# hundredsteppers.net
KiCad netlist of a schematic drawn in EAGLE
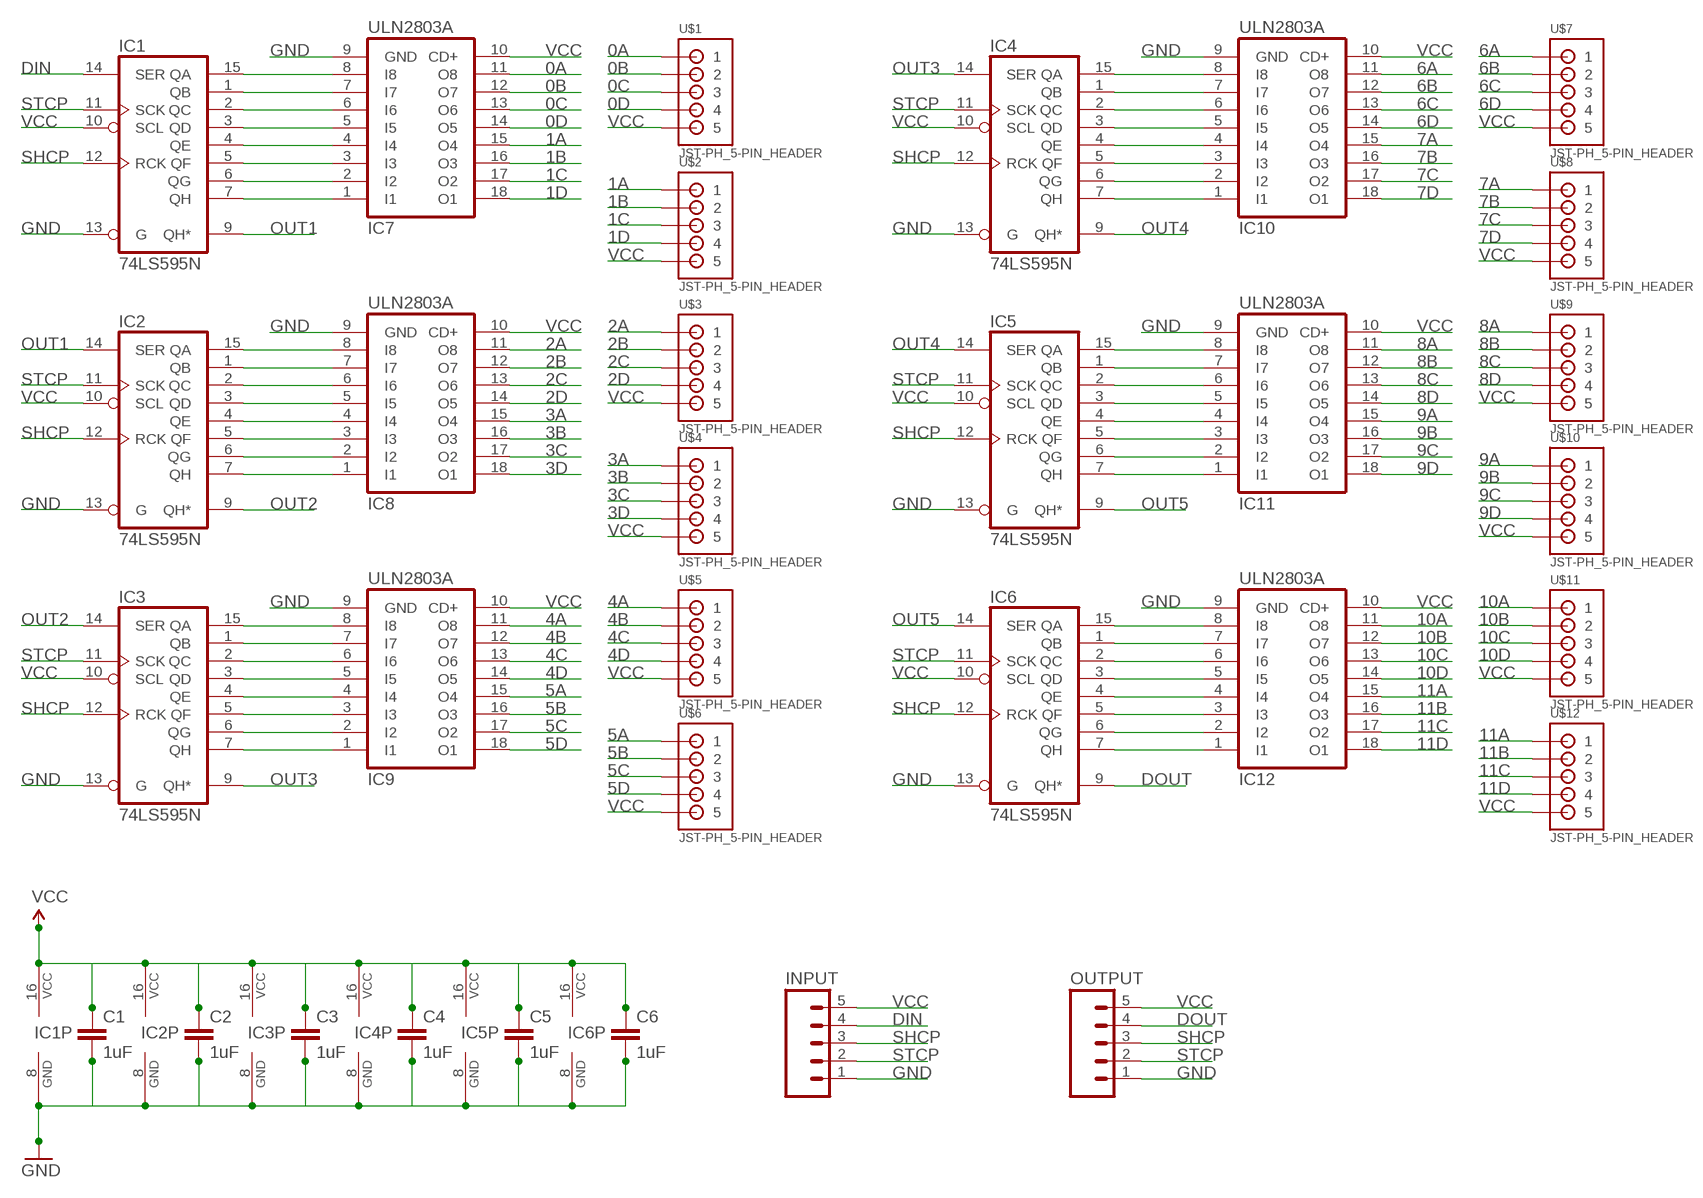
[diagram p0: schematic, sheet 1]

(export (version "E")
  (design (tool "Eeschema 10.0.6"))
  (components
    (comp (ref "C1")
      (value "1uF")
      (footprint "eagle-import:0805")
      (libsource (lib "eagle-import") (part "1UF-25V-10%(0805)"))
    )
    (comp (ref "C2")
      (value "1uF")
      (footprint "eagle-import:0805")
      (libsource (lib "eagle-import") (part "1UF-25V-10%(0805)"))
    )
    (comp (ref "C3")
      (value "1uF")
      (footprint "eagle-import:0805")
      (libsource (lib "eagle-import") (part "1UF-25V-10%(0805)"))
    )
    (comp (ref "C4")
      (value "1uF")
      (footprint "eagle-import:0805")
      (libsource (lib "eagle-import") (part "1UF-25V-10%(0805)"))
    )
    (comp (ref "C5")
      (value "1uF")
      (footprint "eagle-import:0805")
      (libsource (lib "eagle-import") (part "1UF-25V-10%(0805)"))
    )
    (comp (ref "C6")
      (value "1uF")
      (footprint "eagle-import:0805")
      (libsource (lib "eagle-import") (part "1UF-25V-10%(0805)"))
    )
    (comp (ref "IC1")
      (value "74LS595N")
      (footprint "eagle-import:DIL16")
      (libsource (lib "eagle-import") (part "74595NLS"))
    )
    (comp (ref "IC2")
      (value "74LS595N")
      (footprint "eagle-import:DIL16")
      (libsource (lib "eagle-import") (part "74595NLS"))
    )
    (comp (ref "IC3")
      (value "74LS595N")
      (footprint "eagle-import:DIL16")
      (libsource (lib "eagle-import") (part "74595NLS"))
    )
    (comp (ref "IC4")
      (value "74LS595N")
      (footprint "eagle-import:DIL16")
      (libsource (lib "eagle-import") (part "74595NLS"))
    )
    (comp (ref "IC5")
      (value "74LS595N")
      (footprint "eagle-import:DIL16")
      (libsource (lib "eagle-import") (part "74595NLS"))
    )
    (comp (ref "IC6")
      (value "74LS595N")
      (footprint "eagle-import:DIL16")
      (libsource (lib "eagle-import") (part "74595NLS"))
    )
    (comp (ref "IC7")
      (value "ULN2803A")
      (footprint "eagle-import:DIL18")
      (libsource (lib "eagle-import") (part "ULN2803A"))
    )
    (comp (ref "IC8")
      (value "ULN2803A")
      (footprint "eagle-import:DIL18")
      (libsource (lib "eagle-import") (part "ULN2803A"))
    )
    (comp (ref "IC9")
      (value "ULN2803A")
      (footprint "eagle-import:DIL18")
      (libsource (lib "eagle-import") (part "ULN2803A"))
    )
    (comp (ref "IC10")
      (value "ULN2803A")
      (footprint "eagle-import:DIL18")
      (libsource (lib "eagle-import") (part "ULN2803A"))
    )
    (comp (ref "IC11")
      (value "ULN2803A")
      (footprint "eagle-import:DIL18")
      (libsource (lib "eagle-import") (part "ULN2803A"))
    )
    (comp (ref "IC12")
      (value "ULN2803A")
      (footprint "eagle-import:DIL18")
      (libsource (lib "eagle-import") (part "ULN2803A"))
    )
    (comp (ref "INPUT")
      (value "M05PTH")
      (footprint "eagle-import:1X05")
      (libsource (lib "eagle-import") (part "M05PTH"))
    )
    (comp (ref "OUTPUT")
      (value "M05PTH")
      (footprint "eagle-import:1X05")
      (libsource (lib "eagle-import") (part "M05PTH"))
    )
    (comp (ref "U$1")
      (value "JST-PH_5-PIN_HEADER")
      (footprint "eagle-import:JST_B5B-PH_HEADER")
      (libsource (lib "eagle-import") (part "JST-PH_5-PIN_HEADER"))
    )
    (comp (ref "U$2")
      (value "JST-PH_5-PIN_HEADER")
      (footprint "eagle-import:JST_B5B-PH_HEADER")
      (libsource (lib "eagle-import") (part "JST-PH_5-PIN_HEADER"))
    )
    (comp (ref "U$3")
      (value "JST-PH_5-PIN_HEADER")
      (footprint "eagle-import:JST_B5B-PH_HEADER")
      (libsource (lib "eagle-import") (part "JST-PH_5-PIN_HEADER"))
    )
    (comp (ref "U$4")
      (value "JST-PH_5-PIN_HEADER")
      (footprint "eagle-import:JST_B5B-PH_HEADER")
      (libsource (lib "eagle-import") (part "JST-PH_5-PIN_HEADER"))
    )
    (comp (ref "U$5")
      (value "JST-PH_5-PIN_HEADER")
      (footprint "eagle-import:JST_B5B-PH_HEADER")
      (libsource (lib "eagle-import") (part "JST-PH_5-PIN_HEADER"))
    )
    (comp (ref "U$6")
      (value "JST-PH_5-PIN_HEADER")
      (footprint "eagle-import:JST_B5B-PH_HEADER")
      (libsource (lib "eagle-import") (part "JST-PH_5-PIN_HEADER"))
    )
    (comp (ref "U$7")
      (value "JST-PH_5-PIN_HEADER")
      (footprint "eagle-import:JST_B5B-PH_HEADER")
      (libsource (lib "eagle-import") (part "JST-PH_5-PIN_HEADER"))
    )
    (comp (ref "U$8")
      (value "JST-PH_5-PIN_HEADER")
      (footprint "eagle-import:JST_B5B-PH_HEADER")
      (libsource (lib "eagle-import") (part "JST-PH_5-PIN_HEADER"))
    )
    (comp (ref "U$9")
      (value "JST-PH_5-PIN_HEADER")
      (footprint "eagle-import:JST_B5B-PH_HEADER")
      (libsource (lib "eagle-import") (part "JST-PH_5-PIN_HEADER"))
    )
    (comp (ref "U$10")
      (value "JST-PH_5-PIN_HEADER")
      (footprint "eagle-import:JST_B5B-PH_HEADER")
      (libsource (lib "eagle-import") (part "JST-PH_5-PIN_HEADER"))
    )
    (comp (ref "U$11")
      (value "JST-PH_5-PIN_HEADER")
      (footprint "eagle-import:JST_B5B-PH_HEADER")
      (libsource (lib "eagle-import") (part "JST-PH_5-PIN_HEADER"))
    )
    (comp (ref "U$12")
      (value "JST-PH_5-PIN_HEADER")
      (footprint "eagle-import:JST_B5B-PH_HEADER")
      (libsource (lib "eagle-import") (part "JST-PH_5-PIN_HEADER"))
    )
  )
  (nets
    (net (code "1") (name "/0A") (class "Default")
      (node (ref "IC7") (pin "11") (pinfunction "O8_11") (pintype "open_collector"))
      (node (ref "U$1") (pin "P1") (pinfunction "1_P1") (pintype "bidirectional"))
    )
    (net (code "2") (name "/0B") (class "Default")
      (node (ref "IC7") (pin "12") (pinfunction "O7_12") (pintype "open_collector"))
      (node (ref "U$1") (pin "P2") (pinfunction "2_P2") (pintype "bidirectional"))
    )
    (net (code "3") (name "/0C") (class "Default")
      (node (ref "IC7") (pin "13") (pinfunction "O6_13") (pintype "open_collector"))
      (node (ref "U$1") (pin "P3") (pinfunction "3_P3") (pintype "bidirectional"))
    )
    (net (code "4") (name "/0D") (class "Default")
      (node (ref "IC7") (pin "14") (pinfunction "O5_14") (pintype "open_collector"))
      (node (ref "U$1") (pin "P4") (pinfunction "4_P4") (pintype "bidirectional"))
    )
    (net (code "5") (name "/1A") (class "Default")
      (node (ref "IC7") (pin "15") (pinfunction "O4_15") (pintype "open_collector"))
      (node (ref "U$2") (pin "P1") (pinfunction "1_P1") (pintype "bidirectional"))
    )
    (net (code "6") (name "/1B") (class "Default")
      (node (ref "IC7") (pin "16") (pinfunction "O3_16") (pintype "open_collector"))
      (node (ref "U$2") (pin "P2") (pinfunction "2_P2") (pintype "bidirectional"))
    )
    (net (code "7") (name "/1C") (class "Default")
      (node (ref "IC7") (pin "17") (pinfunction "O2_17") (pintype "open_collector"))
      (node (ref "U$2") (pin "P3") (pinfunction "3_P3") (pintype "bidirectional"))
    )
    (net (code "8") (name "/1D") (class "Default")
      (node (ref "IC7") (pin "18") (pinfunction "O1_18") (pintype "open_collector"))
      (node (ref "U$2") (pin "P4") (pinfunction "4_P4") (pintype "bidirectional"))
    )
    (net (code "9") (name "/2A") (class "Default")
      (node (ref "IC8") (pin "11") (pinfunction "O8_11") (pintype "open_collector"))
      (node (ref "U$3") (pin "P1") (pinfunction "1_P1") (pintype "bidirectional"))
    )
    (net (code "10") (name "/2B") (class "Default")
      (node (ref "IC8") (pin "12") (pinfunction "O7_12") (pintype "open_collector"))
      (node (ref "U$3") (pin "P2") (pinfunction "2_P2") (pintype "bidirectional"))
    )
    (net (code "11") (name "/2C") (class "Default")
      (node (ref "IC8") (pin "13") (pinfunction "O6_13") (pintype "open_collector"))
      (node (ref "U$3") (pin "P3") (pinfunction "3_P3") (pintype "bidirectional"))
    )
    (net (code "12") (name "/2D") (class "Default")
      (node (ref "IC8") (pin "14") (pinfunction "O5_14") (pintype "open_collector"))
      (node (ref "U$3") (pin "P4") (pinfunction "4_P4") (pintype "bidirectional"))
    )
    (net (code "13") (name "/3A") (class "Default")
      (node (ref "IC8") (pin "15") (pinfunction "O4_15") (pintype "open_collector"))
      (node (ref "U$4") (pin "P1") (pinfunction "1_P1") (pintype "bidirectional"))
    )
    (net (code "14") (name "/3B") (class "Default")
      (node (ref "IC8") (pin "16") (pinfunction "O3_16") (pintype "open_collector"))
      (node (ref "U$4") (pin "P2") (pinfunction "2_P2") (pintype "bidirectional"))
    )
    (net (code "15") (name "/3C") (class "Default")
      (node (ref "IC8") (pin "17") (pinfunction "O2_17") (pintype "open_collector"))
      (node (ref "U$4") (pin "P3") (pinfunction "3_P3") (pintype "bidirectional"))
    )
    (net (code "16") (name "/3D") (class "Default")
      (node (ref "IC8") (pin "18") (pinfunction "O1_18") (pintype "open_collector"))
      (node (ref "U$4") (pin "P4") (pinfunction "4_P4") (pintype "bidirectional"))
    )
    (net (code "17") (name "/4A") (class "Default")
      (node (ref "IC9") (pin "11") (pinfunction "O8_11") (pintype "open_collector"))
      (node (ref "U$5") (pin "P1") (pinfunction "1_P1") (pintype "bidirectional"))
    )
    (net (code "18") (name "/4B") (class "Default")
      (node (ref "IC9") (pin "12") (pinfunction "O7_12") (pintype "open_collector"))
      (node (ref "U$5") (pin "P2") (pinfunction "2_P2") (pintype "bidirectional"))
    )
    (net (code "19") (name "/4C") (class "Default")
      (node (ref "IC9") (pin "13") (pinfunction "O6_13") (pintype "open_collector"))
      (node (ref "U$5") (pin "P3") (pinfunction "3_P3") (pintype "bidirectional"))
    )
    (net (code "20") (name "/4D") (class "Default")
      (node (ref "IC9") (pin "14") (pinfunction "O5_14") (pintype "open_collector"))
      (node (ref "U$5") (pin "P4") (pinfunction "4_P4") (pintype "bidirectional"))
    )
    (net (code "21") (name "/5A") (class "Default")
      (node (ref "IC9") (pin "15") (pinfunction "O4_15") (pintype "open_collector"))
      (node (ref "U$6") (pin "P1") (pinfunction "1_P1") (pintype "bidirectional"))
    )
    (net (code "22") (name "/5B") (class "Default")
      (node (ref "IC9") (pin "16") (pinfunction "O3_16") (pintype "open_collector"))
      (node (ref "U$6") (pin "P2") (pinfunction "2_P2") (pintype "bidirectional"))
    )
    (net (code "23") (name "/5C") (class "Default")
      (node (ref "IC9") (pin "17") (pinfunction "O2_17") (pintype "open_collector"))
      (node (ref "U$6") (pin "P3") (pinfunction "3_P3") (pintype "bidirectional"))
    )
    (net (code "24") (name "/5D") (class "Default")
      (node (ref "IC9") (pin "18") (pinfunction "O1_18") (pintype "open_collector"))
      (node (ref "U$6") (pin "P4") (pinfunction "4_P4") (pintype "bidirectional"))
    )
    (net (code "25") (name "/6A") (class "Default")
      (node (ref "IC10") (pin "11") (pinfunction "O8_11") (pintype "open_collector"))
      (node (ref "U$7") (pin "P1") (pinfunction "1_P1") (pintype "bidirectional"))
    )
    (net (code "26") (name "/6B") (class "Default")
      (node (ref "IC10") (pin "12") (pinfunction "O7_12") (pintype "open_collector"))
      (node (ref "U$7") (pin "P2") (pinfunction "2_P2") (pintype "bidirectional"))
    )
    (net (code "27") (name "/6C") (class "Default")
      (node (ref "IC10") (pin "13") (pinfunction "O6_13") (pintype "open_collector"))
      (node (ref "U$7") (pin "P3") (pinfunction "3_P3") (pintype "bidirectional"))
    )
    (net (code "28") (name "/6D") (class "Default")
      (node (ref "IC10") (pin "14") (pinfunction "O5_14") (pintype "open_collector"))
      (node (ref "U$7") (pin "P4") (pinfunction "4_P4") (pintype "bidirectional"))
    )
    (net (code "29") (name "/7A") (class "Default")
      (node (ref "IC10") (pin "15") (pinfunction "O4_15") (pintype "open_collector"))
      (node (ref "U$8") (pin "P1") (pinfunction "1_P1") (pintype "bidirectional"))
    )
    (net (code "30") (name "/7B") (class "Default")
      (node (ref "IC10") (pin "16") (pinfunction "O3_16") (pintype "open_collector"))
      (node (ref "U$8") (pin "P2") (pinfunction "2_P2") (pintype "bidirectional"))
    )
    (net (code "31") (name "/7C") (class "Default")
      (node (ref "IC10") (pin "17") (pinfunction "O2_17") (pintype "open_collector"))
      (node (ref "U$8") (pin "P3") (pinfunction "3_P3") (pintype "bidirectional"))
    )
    (net (code "32") (name "/7D") (class "Default")
      (node (ref "IC10") (pin "18") (pinfunction "O1_18") (pintype "open_collector"))
      (node (ref "U$8") (pin "P4") (pinfunction "4_P4") (pintype "bidirectional"))
    )
    (net (code "33") (name "/8A") (class "Default")
      (node (ref "IC11") (pin "11") (pinfunction "O8_11") (pintype "open_collector"))
      (node (ref "U$9") (pin "P1") (pinfunction "1_P1") (pintype "bidirectional"))
    )
    (net (code "34") (name "/8B") (class "Default")
      (node (ref "IC11") (pin "12") (pinfunction "O7_12") (pintype "open_collector"))
      (node (ref "U$9") (pin "P2") (pinfunction "2_P2") (pintype "bidirectional"))
    )
    (net (code "35") (name "/8C") (class "Default")
      (node (ref "IC11") (pin "13") (pinfunction "O6_13") (pintype "open_collector"))
      (node (ref "U$9") (pin "P3") (pinfunction "3_P3") (pintype "bidirectional"))
    )
    (net (code "36") (name "/8D") (class "Default")
      (node (ref "IC11") (pin "14") (pinfunction "O5_14") (pintype "open_collector"))
      (node (ref "U$9") (pin "P4") (pinfunction "4_P4") (pintype "bidirectional"))
    )
    (net (code "37") (name "/9A") (class "Default")
      (node (ref "IC11") (pin "15") (pinfunction "O4_15") (pintype "open_collector"))
      (node (ref "U$10") (pin "P1") (pinfunction "1_P1") (pintype "bidirectional"))
    )
    (net (code "38") (name "/9B") (class "Default")
      (node (ref "IC11") (pin "16") (pinfunction "O3_16") (pintype "open_collector"))
      (node (ref "U$10") (pin "P2") (pinfunction "2_P2") (pintype "bidirectional"))
    )
    (net (code "39") (name "/9C") (class "Default")
      (node (ref "IC11") (pin "17") (pinfunction "O2_17") (pintype "open_collector"))
      (node (ref "U$10") (pin "P3") (pinfunction "3_P3") (pintype "bidirectional"))
    )
    (net (code "40") (name "/9D") (class "Default")
      (node (ref "IC11") (pin "18") (pinfunction "O1_18") (pintype "open_collector"))
      (node (ref "U$10") (pin "P4") (pinfunction "4_P4") (pintype "bidirectional"))
    )
    (net (code "41") (name "/10A") (class "Default")
      (node (ref "IC12") (pin "11") (pinfunction "O8_11") (pintype "open_collector"))
      (node (ref "U$11") (pin "P1") (pinfunction "1_P1") (pintype "bidirectional"))
    )
    (net (code "42") (name "/10B") (class "Default")
      (node (ref "IC12") (pin "12") (pinfunction "O7_12") (pintype "open_collector"))
      (node (ref "U$11") (pin "P2") (pinfunction "2_P2") (pintype "bidirectional"))
    )
    (net (code "43") (name "/10C") (class "Default")
      (node (ref "IC12") (pin "13") (pinfunction "O6_13") (pintype "open_collector"))
      (node (ref "U$11") (pin "P3") (pinfunction "3_P3") (pintype "bidirectional"))
    )
    (net (code "44") (name "/10D") (class "Default")
      (node (ref "IC12") (pin "14") (pinfunction "O5_14") (pintype "open_collector"))
      (node (ref "U$11") (pin "P4") (pinfunction "4_P4") (pintype "bidirectional"))
    )
    (net (code "45") (name "/11A") (class "Default")
      (node (ref "IC12") (pin "15") (pinfunction "O4_15") (pintype "open_collector"))
      (node (ref "U$12") (pin "P1") (pinfunction "1_P1") (pintype "bidirectional"))
    )
    (net (code "46") (name "/11B") (class "Default")
      (node (ref "IC12") (pin "16") (pinfunction "O3_16") (pintype "open_collector"))
      (node (ref "U$12") (pin "P2") (pinfunction "2_P2") (pintype "bidirectional"))
    )
    (net (code "47") (name "/11C") (class "Default")
      (node (ref "IC12") (pin "17") (pinfunction "O2_17") (pintype "open_collector"))
      (node (ref "U$12") (pin "P3") (pinfunction "3_P3") (pintype "bidirectional"))
    )
    (net (code "48") (name "/11D") (class "Default")
      (node (ref "IC12") (pin "18") (pinfunction "O1_18") (pintype "open_collector"))
      (node (ref "U$12") (pin "P4") (pinfunction "4_P4") (pintype "bidirectional"))
    )
    (net (code "49") (name "/DIN") (class "Default")
      (node (ref "IC1") (pin "14") (pinfunction "SER_14") (pintype "input"))
      (node (ref "INPUT") (pin "4") (pinfunction "4_4") (pintype "passive"))
    )
    (net (code "50") (name "/DOUT") (class "Default")
      (node (ref "IC6") (pin "9") (pinfunction "QH*_9") (pintype "tri_state"))
      (node (ref "OUTPUT") (pin "4") (pinfunction "4_4") (pintype "passive"))
    )
    (net (code "51") (name "/OUT1") (class "Default")
      (node (ref "IC1") (pin "9") (pinfunction "QH*_9") (pintype "tri_state"))
      (node (ref "IC2") (pin "14") (pinfunction "SER_14") (pintype "input"))
    )
    (net (code "52") (name "/OUT2") (class "Default")
      (node (ref "IC2") (pin "9") (pinfunction "QH*_9") (pintype "tri_state"))
      (node (ref "IC3") (pin "14") (pinfunction "SER_14") (pintype "input"))
    )
    (net (code "53") (name "/OUT3") (class "Default")
      (node (ref "IC3") (pin "9") (pinfunction "QH*_9") (pintype "tri_state"))
      (node (ref "IC4") (pin "14") (pinfunction "SER_14") (pintype "input"))
    )
    (net (code "54") (name "/OUT4") (class "Default")
      (node (ref "IC4") (pin "9") (pinfunction "QH*_9") (pintype "tri_state"))
      (node (ref "IC5") (pin "14") (pinfunction "SER_14") (pintype "input"))
    )
    (net (code "55") (name "/OUT5") (class "Default")
      (node (ref "IC5") (pin "9") (pinfunction "QH*_9") (pintype "tri_state"))
      (node (ref "IC6") (pin "14") (pinfunction "SER_14") (pintype "input"))
    )
    (net (code "56") (name "/SHCP") (class "Default")
      (node (ref "IC1") (pin "12") (pinfunction "RCK_12") (pintype "input"))
      (node (ref "IC2") (pin "12") (pinfunction "RCK_12") (pintype "input"))
      (node (ref "IC3") (pin "12") (pinfunction "RCK_12") (pintype "input"))
      (node (ref "IC4") (pin "12") (pinfunction "RCK_12") (pintype "input"))
      (node (ref "IC5") (pin "12") (pinfunction "RCK_12") (pintype "input"))
      (node (ref "IC6") (pin "12") (pinfunction "RCK_12") (pintype "input"))
      (node (ref "INPUT") (pin "3") (pinfunction "3_3") (pintype "passive"))
      (node (ref "OUTPUT") (pin "3") (pinfunction "3_3") (pintype "passive"))
    )
    (net (code "57") (name "/STCP") (class "Default")
      (node (ref "IC1") (pin "11") (pinfunction "SCK_11") (pintype "input"))
      (node (ref "IC2") (pin "11") (pinfunction "SCK_11") (pintype "input"))
      (node (ref "IC3") (pin "11") (pinfunction "SCK_11") (pintype "input"))
      (node (ref "IC4") (pin "11") (pinfunction "SCK_11") (pintype "input"))
      (node (ref "IC5") (pin "11") (pinfunction "SCK_11") (pintype "input"))
      (node (ref "IC6") (pin "11") (pinfunction "SCK_11") (pintype "input"))
      (node (ref "INPUT") (pin "2") (pinfunction "2_2") (pintype "passive"))
      (node (ref "OUTPUT") (pin "2") (pinfunction "2_2") (pintype "passive"))
    )
    (net (code "58") (name "GND") (class "Default")
      (node (ref "C1") (pin "2") (pinfunction "2_2") (pintype "passive"))
      (node (ref "C2") (pin "2") (pinfunction "2_2") (pintype "passive"))
      (node (ref "C3") (pin "2") (pinfunction "2_2") (pintype "passive"))
      (node (ref "C4") (pin "2") (pinfunction "2_2") (pintype "passive"))
      (node (ref "C5") (pin "2") (pinfunction "2_2") (pintype "passive"))
      (node (ref "C6") (pin "2") (pinfunction "2_2") (pintype "passive"))
      (node (ref "IC1") (pin "13") (pinfunction "G_13") (pintype "input"))
      (node (ref "IC1") (pin "8") (pinfunction "GND_8") (pintype "power_in"))
      (node (ref "IC10") (pin "9") (pinfunction "GND_9") (pintype "power_in"))
      (node (ref "IC11") (pin "9") (pinfunction "GND_9") (pintype "power_in"))
      (node (ref "IC12") (pin "9") (pinfunction "GND_9") (pintype "power_in"))
      (node (ref "IC2") (pin "13") (pinfunction "G_13") (pintype "input"))
      (node (ref "IC2") (pin "8") (pinfunction "GND_8") (pintype "power_in"))
      (node (ref "IC3") (pin "13") (pinfunction "G_13") (pintype "input"))
      (node (ref "IC3") (pin "8") (pinfunction "GND_8") (pintype "power_in"))
      (node (ref "IC4") (pin "13") (pinfunction "G_13") (pintype "input"))
      (node (ref "IC4") (pin "8") (pinfunction "GND_8") (pintype "power_in"))
      (node (ref "IC5") (pin "13") (pinfunction "G_13") (pintype "input"))
      (node (ref "IC5") (pin "8") (pinfunction "GND_8") (pintype "power_in"))
      (node (ref "IC6") (pin "13") (pinfunction "G_13") (pintype "input"))
      (node (ref "IC6") (pin "8") (pinfunction "GND_8") (pintype "power_in"))
      (node (ref "IC7") (pin "9") (pinfunction "GND_9") (pintype "power_in"))
      (node (ref "IC8") (pin "9") (pinfunction "GND_9") (pintype "power_in"))
      (node (ref "IC9") (pin "9") (pinfunction "GND_9") (pintype "power_in"))
      (node (ref "INPUT") (pin "1") (pinfunction "1_1") (pintype "passive"))
      (node (ref "OUTPUT") (pin "1") (pinfunction "1_1") (pintype "passive"))
    )
    (net (code "59") (name "Net-(IC1A-QA)") (class "Default")
      (node (ref "IC1") (pin "15") (pinfunction "QA_15") (pintype "tri_state"))
      (node (ref "IC7") (pin "8") (pinfunction "I8_8") (pintype "input"))
    )
    (net (code "60") (name "Net-(IC1A-QB)") (class "Default")
      (node (ref "IC1") (pin "1") (pinfunction "QB_1") (pintype "tri_state"))
      (node (ref "IC7") (pin "7") (pinfunction "I7_7") (pintype "input"))
    )
    (net (code "61") (name "Net-(IC1A-QC)") (class "Default")
      (node (ref "IC1") (pin "2") (pinfunction "QC_2") (pintype "tri_state"))
      (node (ref "IC7") (pin "6") (pinfunction "I6_6") (pintype "input"))
    )
    (net (code "62") (name "Net-(IC1A-QD)") (class "Default")
      (node (ref "IC1") (pin "3") (pinfunction "QD_3") (pintype "tri_state"))
      (node (ref "IC7") (pin "5") (pinfunction "I5_5") (pintype "input"))
    )
    (net (code "63") (name "Net-(IC1A-QE)") (class "Default")
      (node (ref "IC1") (pin "4") (pinfunction "QE_4") (pintype "tri_state"))
      (node (ref "IC7") (pin "4") (pinfunction "I4_4") (pintype "input"))
    )
    (net (code "64") (name "Net-(IC1A-QF)") (class "Default")
      (node (ref "IC1") (pin "5") (pinfunction "QF_5") (pintype "tri_state"))
      (node (ref "IC7") (pin "3") (pinfunction "I3_3") (pintype "input"))
    )
    (net (code "65") (name "Net-(IC1A-QG)") (class "Default")
      (node (ref "IC1") (pin "6") (pinfunction "QG_6") (pintype "tri_state"))
      (node (ref "IC7") (pin "2") (pinfunction "I2_2") (pintype "input"))
    )
    (net (code "66") (name "Net-(IC1A-QH)") (class "Default")
      (node (ref "IC1") (pin "7") (pinfunction "QH_7") (pintype "tri_state"))
      (node (ref "IC7") (pin "1") (pinfunction "I1_1") (pintype "input"))
    )
    (net (code "67") (name "Net-(IC2A-QA)") (class "Default")
      (node (ref "IC2") (pin "15") (pinfunction "QA_15") (pintype "tri_state"))
      (node (ref "IC8") (pin "8") (pinfunction "I8_8") (pintype "input"))
    )
    (net (code "68") (name "Net-(IC2A-QB)") (class "Default")
      (node (ref "IC2") (pin "1") (pinfunction "QB_1") (pintype "tri_state"))
      (node (ref "IC8") (pin "7") (pinfunction "I7_7") (pintype "input"))
    )
    (net (code "69") (name "Net-(IC2A-QC)") (class "Default")
      (node (ref "IC2") (pin "2") (pinfunction "QC_2") (pintype "tri_state"))
      (node (ref "IC8") (pin "6") (pinfunction "I6_6") (pintype "input"))
    )
    (net (code "70") (name "Net-(IC2A-QD)") (class "Default")
      (node (ref "IC2") (pin "3") (pinfunction "QD_3") (pintype "tri_state"))
      (node (ref "IC8") (pin "5") (pinfunction "I5_5") (pintype "input"))
    )
    (net (code "71") (name "Net-(IC2A-QE)") (class "Default")
      (node (ref "IC2") (pin "4") (pinfunction "QE_4") (pintype "tri_state"))
      (node (ref "IC8") (pin "4") (pinfunction "I4_4") (pintype "input"))
    )
    (net (code "72") (name "Net-(IC2A-QF)") (class "Default")
      (node (ref "IC2") (pin "5") (pinfunction "QF_5") (pintype "tri_state"))
      (node (ref "IC8") (pin "3") (pinfunction "I3_3") (pintype "input"))
    )
    (net (code "73") (name "Net-(IC2A-QG)") (class "Default")
      (node (ref "IC2") (pin "6") (pinfunction "QG_6") (pintype "tri_state"))
      (node (ref "IC8") (pin "2") (pinfunction "I2_2") (pintype "input"))
    )
    (net (code "74") (name "Net-(IC2A-QH)") (class "Default")
      (node (ref "IC2") (pin "7") (pinfunction "QH_7") (pintype "tri_state"))
      (node (ref "IC8") (pin "1") (pinfunction "I1_1") (pintype "input"))
    )
    (net (code "75") (name "Net-(IC3A-QA)") (class "Default")
      (node (ref "IC3") (pin "15") (pinfunction "QA_15") (pintype "tri_state"))
      (node (ref "IC9") (pin "8") (pinfunction "I8_8") (pintype "input"))
    )
    (net (code "76") (name "Net-(IC3A-QB)") (class "Default")
      (node (ref "IC3") (pin "1") (pinfunction "QB_1") (pintype "tri_state"))
      (node (ref "IC9") (pin "7") (pinfunction "I7_7") (pintype "input"))
    )
    (net (code "77") (name "Net-(IC3A-QC)") (class "Default")
      (node (ref "IC3") (pin "2") (pinfunction "QC_2") (pintype "tri_state"))
      (node (ref "IC9") (pin "6") (pinfunction "I6_6") (pintype "input"))
    )
    (net (code "78") (name "Net-(IC3A-QD)") (class "Default")
      (node (ref "IC3") (pin "3") (pinfunction "QD_3") (pintype "tri_state"))
      (node (ref "IC9") (pin "5") (pinfunction "I5_5") (pintype "input"))
    )
    (net (code "79") (name "Net-(IC3A-QE)") (class "Default")
      (node (ref "IC3") (pin "4") (pinfunction "QE_4") (pintype "tri_state"))
      (node (ref "IC9") (pin "4") (pinfunction "I4_4") (pintype "input"))
    )
    (net (code "80") (name "Net-(IC3A-QF)") (class "Default")
      (node (ref "IC3") (pin "5") (pinfunction "QF_5") (pintype "tri_state"))
      (node (ref "IC9") (pin "3") (pinfunction "I3_3") (pintype "input"))
    )
    (net (code "81") (name "Net-(IC3A-QG)") (class "Default")
      (node (ref "IC3") (pin "6") (pinfunction "QG_6") (pintype "tri_state"))
      (node (ref "IC9") (pin "2") (pinfunction "I2_2") (pintype "input"))
    )
    (net (code "82") (name "Net-(IC3A-QH)") (class "Default")
      (node (ref "IC3") (pin "7") (pinfunction "QH_7") (pintype "tri_state"))
      (node (ref "IC9") (pin "1") (pinfunction "I1_1") (pintype "input"))
    )
    (net (code "83") (name "Net-(IC10-I1)") (class "Default")
      (node (ref "IC10") (pin "1") (pinfunction "I1_1") (pintype "input"))
      (node (ref "IC4") (pin "7") (pinfunction "QH_7") (pintype "tri_state"))
    )
    (net (code "84") (name "Net-(IC10-I2)") (class "Default")
      (node (ref "IC10") (pin "2") (pinfunction "I2_2") (pintype "input"))
      (node (ref "IC4") (pin "6") (pinfunction "QG_6") (pintype "tri_state"))
    )
    (net (code "85") (name "Net-(IC10-I3)") (class "Default")
      (node (ref "IC10") (pin "3") (pinfunction "I3_3") (pintype "input"))
      (node (ref "IC4") (pin "5") (pinfunction "QF_5") (pintype "tri_state"))
    )
    (net (code "86") (name "Net-(IC10-I4)") (class "Default")
      (node (ref "IC10") (pin "4") (pinfunction "I4_4") (pintype "input"))
      (node (ref "IC4") (pin "4") (pinfunction "QE_4") (pintype "tri_state"))
    )
    (net (code "87") (name "Net-(IC10-I5)") (class "Default")
      (node (ref "IC10") (pin "5") (pinfunction "I5_5") (pintype "input"))
      (node (ref "IC4") (pin "3") (pinfunction "QD_3") (pintype "tri_state"))
    )
    (net (code "88") (name "Net-(IC10-I6)") (class "Default")
      (node (ref "IC10") (pin "6") (pinfunction "I6_6") (pintype "input"))
      (node (ref "IC4") (pin "2") (pinfunction "QC_2") (pintype "tri_state"))
    )
    (net (code "89") (name "Net-(IC10-I7)") (class "Default")
      (node (ref "IC10") (pin "7") (pinfunction "I7_7") (pintype "input"))
      (node (ref "IC4") (pin "1") (pinfunction "QB_1") (pintype "tri_state"))
    )
    (net (code "90") (name "Net-(IC10-I8)") (class "Default")
      (node (ref "IC10") (pin "8") (pinfunction "I8_8") (pintype "input"))
      (node (ref "IC4") (pin "15") (pinfunction "QA_15") (pintype "tri_state"))
    )
    (net (code "91") (name "Net-(IC11-I1)") (class "Default")
      (node (ref "IC11") (pin "1") (pinfunction "I1_1") (pintype "input"))
      (node (ref "IC5") (pin "7") (pinfunction "QH_7") (pintype "tri_state"))
    )
    (net (code "92") (name "Net-(IC11-I2)") (class "Default")
      (node (ref "IC11") (pin "2") (pinfunction "I2_2") (pintype "input"))
      (node (ref "IC5") (pin "6") (pinfunction "QG_6") (pintype "tri_state"))
    )
    (net (code "93") (name "Net-(IC11-I3)") (class "Default")
      (node (ref "IC11") (pin "3") (pinfunction "I3_3") (pintype "input"))
      (node (ref "IC5") (pin "5") (pinfunction "QF_5") (pintype "tri_state"))
    )
    (net (code "94") (name "Net-(IC11-I4)") (class "Default")
      (node (ref "IC11") (pin "4") (pinfunction "I4_4") (pintype "input"))
      (node (ref "IC5") (pin "4") (pinfunction "QE_4") (pintype "tri_state"))
    )
    (net (code "95") (name "Net-(IC11-I5)") (class "Default")
      (node (ref "IC11") (pin "5") (pinfunction "I5_5") (pintype "input"))
      (node (ref "IC5") (pin "3") (pinfunction "QD_3") (pintype "tri_state"))
    )
    (net (code "96") (name "Net-(IC11-I6)") (class "Default")
      (node (ref "IC11") (pin "6") (pinfunction "I6_6") (pintype "input"))
      (node (ref "IC5") (pin "2") (pinfunction "QC_2") (pintype "tri_state"))
    )
    (net (code "97") (name "Net-(IC11-I7)") (class "Default")
      (node (ref "IC11") (pin "7") (pinfunction "I7_7") (pintype "input"))
      (node (ref "IC5") (pin "1") (pinfunction "QB_1") (pintype "tri_state"))
    )
    (net (code "98") (name "Net-(IC11-I8)") (class "Default")
      (node (ref "IC11") (pin "8") (pinfunction "I8_8") (pintype "input"))
      (node (ref "IC5") (pin "15") (pinfunction "QA_15") (pintype "tri_state"))
    )
    (net (code "99") (name "Net-(IC12-I1)") (class "Default")
      (node (ref "IC12") (pin "1") (pinfunction "I1_1") (pintype "input"))
      (node (ref "IC6") (pin "7") (pinfunction "QH_7") (pintype "tri_state"))
    )
    (net (code "100") (name "Net-(IC12-I2)") (class "Default")
      (node (ref "IC12") (pin "2") (pinfunction "I2_2") (pintype "input"))
      (node (ref "IC6") (pin "6") (pinfunction "QG_6") (pintype "tri_state"))
    )
    (net (code "101") (name "Net-(IC12-I3)") (class "Default")
      (node (ref "IC12") (pin "3") (pinfunction "I3_3") (pintype "input"))
      (node (ref "IC6") (pin "5") (pinfunction "QF_5") (pintype "tri_state"))
    )
    (net (code "102") (name "Net-(IC12-I4)") (class "Default")
      (node (ref "IC12") (pin "4") (pinfunction "I4_4") (pintype "input"))
      (node (ref "IC6") (pin "4") (pinfunction "QE_4") (pintype "tri_state"))
    )
    (net (code "103") (name "Net-(IC12-I5)") (class "Default")
      (node (ref "IC12") (pin "5") (pinfunction "I5_5") (pintype "input"))
      (node (ref "IC6") (pin "3") (pinfunction "QD_3") (pintype "tri_state"))
    )
    (net (code "104") (name "Net-(IC12-I6)") (class "Default")
      (node (ref "IC12") (pin "6") (pinfunction "I6_6") (pintype "input"))
      (node (ref "IC6") (pin "2") (pinfunction "QC_2") (pintype "tri_state"))
    )
    (net (code "105") (name "Net-(IC12-I7)") (class "Default")
      (node (ref "IC12") (pin "7") (pinfunction "I7_7") (pintype "input"))
      (node (ref "IC6") (pin "1") (pinfunction "QB_1") (pintype "tri_state"))
    )
    (net (code "106") (name "Net-(IC12-I8)") (class "Default")
      (node (ref "IC12") (pin "8") (pinfunction "I8_8") (pintype "input"))
      (node (ref "IC6") (pin "15") (pinfunction "QA_15") (pintype "tri_state"))
    )
    (net (code "107") (name "VCC") (class "Default")
      (node (ref "C1") (pin "1") (pinfunction "1_1") (pintype "passive"))
      (node (ref "C2") (pin "1") (pinfunction "1_1") (pintype "passive"))
      (node (ref "C3") (pin "1") (pinfunction "1_1") (pintype "passive"))
      (node (ref "C4") (pin "1") (pinfunction "1_1") (pintype "passive"))
      (node (ref "C5") (pin "1") (pinfunction "1_1") (pintype "passive"))
      (node (ref "C6") (pin "1") (pinfunction "1_1") (pintype "passive"))
      (node (ref "IC1") (pin "10") (pinfunction "SCL_10") (pintype "input"))
      (node (ref "IC1") (pin "16") (pinfunction "VCC_16") (pintype "power_in"))
      (node (ref "IC10") (pin "10") (pinfunction "CD+_10") (pintype "passive"))
      (node (ref "IC11") (pin "10") (pinfunction "CD+_10") (pintype "passive"))
      (node (ref "IC12") (pin "10") (pinfunction "CD+_10") (pintype "passive"))
      (node (ref "IC2") (pin "10") (pinfunction "SCL_10") (pintype "input"))
      (node (ref "IC2") (pin "16") (pinfunction "VCC_16") (pintype "power_in"))
      (node (ref "IC3") (pin "10") (pinfunction "SCL_10") (pintype "input"))
      (node (ref "IC3") (pin "16") (pinfunction "VCC_16") (pintype "power_in"))
      (node (ref "IC4") (pin "10") (pinfunction "SCL_10") (pintype "input"))
      (node (ref "IC4") (pin "16") (pinfunction "VCC_16") (pintype "power_in"))
      (node (ref "IC5") (pin "10") (pinfunction "SCL_10") (pintype "input"))
      (node (ref "IC5") (pin "16") (pinfunction "VCC_16") (pintype "power_in"))
      (node (ref "IC6") (pin "10") (pinfunction "SCL_10") (pintype "input"))
      (node (ref "IC6") (pin "16") (pinfunction "VCC_16") (pintype "power_in"))
      (node (ref "IC7") (pin "10") (pinfunction "CD+_10") (pintype "passive"))
      (node (ref "IC8") (pin "10") (pinfunction "CD+_10") (pintype "passive"))
      (node (ref "IC9") (pin "10") (pinfunction "CD+_10") (pintype "passive"))
      (node (ref "INPUT") (pin "5") (pinfunction "5_5") (pintype "passive"))
      (node (ref "OUTPUT") (pin "5") (pinfunction "5_5") (pintype "passive"))
      (node (ref "U$1") (pin "P5") (pinfunction "5_P5") (pintype "bidirectional"))
      (node (ref "U$10") (pin "P5") (pinfunction "5_P5") (pintype "bidirectional"))
      (node (ref "U$11") (pin "P5") (pinfunction "5_P5") (pintype "bidirectional"))
      (node (ref "U$12") (pin "P5") (pinfunction "5_P5") (pintype "bidirectional"))
      (node (ref "U$2") (pin "P5") (pinfunction "5_P5") (pintype "bidirectional"))
      (node (ref "U$3") (pin "P5") (pinfunction "5_P5") (pintype "bidirectional"))
      (node (ref "U$4") (pin "P5") (pinfunction "5_P5") (pintype "bidirectional"))
      (node (ref "U$5") (pin "P5") (pinfunction "5_P5") (pintype "bidirectional"))
      (node (ref "U$6") (pin "P5") (pinfunction "5_P5") (pintype "bidirectional"))
      (node (ref "U$7") (pin "P5") (pinfunction "5_P5") (pintype "bidirectional"))
      (node (ref "U$8") (pin "P5") (pinfunction "5_P5") (pintype "bidirectional"))
      (node (ref "U$9") (pin "P5") (pinfunction "5_P5") (pintype "bidirectional"))
    )
  )
)
